# MainConnector.net
KiCad netlist of a schematic drawn in Altium Designer
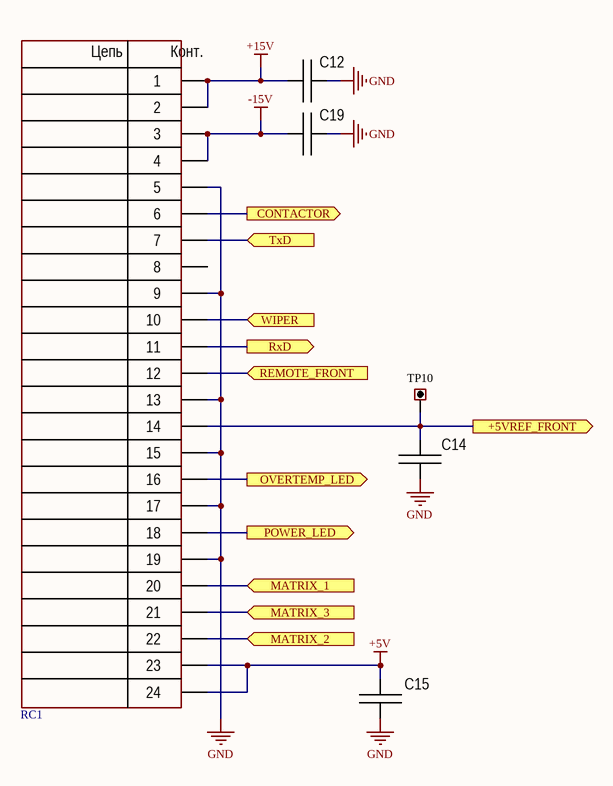
[diagram p0: MainConnector.SchDoc]

(export (version "E")
  (design (tool "Eeschema 10.0.6"))
  (components
    (comp (ref "C12")
      (value "~")
      (footprint "StandardCase:CAP: 1206")
      (fields
        (field (name "MANUFACTURER") "Yageo")
        (field (name "PARTNUMBER") "CC1206KRX7R9BB104")
        (field (name "VALUEMANUFACTURERPARTNUMBER") "Ceramic capacitor, 0.1μF, 1206")
      )
      (libsource (lib "Capacitor") (part "Ceramic_1206"))
    )
    (comp (ref "C14")
      (value "~")
      (footprint "StandardCase:CAP: 1206")
      (fields
        (field (name "MANUFACTURER") "Yageo")
        (field (name "PARTNUMBER") "CC1206KRX7R9BB104")
        (field (name "VALUEMANUFACTURERPARTNUMBER") "Ceramic capacitor, 0.1μF, 1206")
      )
      (libsource (lib "Capacitor") (part "Ceramic_1206"))
    )
    (comp (ref "C15")
      (value "~")
      (footprint "StandardCase:CAP: 1206")
      (fields
        (field (name "MANUFACTURER") "Yageo")
        (field (name "PARTNUMBER") "CC1206KRX7R9BB104")
        (field (name "VALUEMANUFACTURERPARTNUMBER") "Ceramic capacitor, 0.1μF, 1206")
      )
      (libsource (lib "Capacitor") (part "Ceramic_1206"))
    )
    (comp (ref "C19")
      (value "~")
      (footprint "StandardCase:CAP: 1206")
      (fields
        (field (name "MANUFACTURER") "Yageo")
        (field (name "PARTNUMBER") "CC1206KRX7R9BB104")
        (field (name "VALUEMANUFACTURERPARTNUMBER") "Ceramic capacitor, 0.1μF, 1206")
      )
      (libsource (lib "Capacitor") (part "Ceramic_1206"))
    )
    (comp (ref "RC1")
      (value "~")
      (footprint "DS1018-24 SIBX")
      (fields
        (field (name "VALUEMANUFACTURERPARTNUMBER") "Connector, DS1018-24 SIBX, 24 pin")
        (field (name "PARTNUMBER") "DS1018-24 SIBX")
      )
      (libsource (lib "FP_lib_SCH") (part "DS1018-24 SIBX"))
    )
    (comp (ref "TP10")
      (value "Test_Point")
      (footprint "FP_lib_PCB:Test_Point")
      (libsource (lib "FP_lib_SCH") (part "Test_Point"))
    )
  )
  (nets
    (net (code "1") (name "+5V") (class "Default")
      (node (ref "C15") (pin "2") (pinfunction "2_2") (pintype "power_in"))
      (node (ref "RC1") (pin "23") (pinfunction "23_23") (pintype "passive"))
      (node (ref "RC1") (pin "24") (pinfunction "24_24") (pintype "passive"))
    )
    (net (code "2") (name "+15V") (class "Default")
      (node (ref "C12") (pin "2") (pinfunction "2_2") (pintype "power_in"))
      (node (ref "RC1") (pin "1") (pinfunction "1_1") (pintype "passive"))
      (node (ref "RC1") (pin "2") (pinfunction "2_2") (pintype "passive"))
    )
    (net (code "3") (name "-15V") (class "Default")
      (node (ref "C19") (pin "1") (pinfunction "1_1") (pintype "power_in"))
      (node (ref "RC1") (pin "3") (pinfunction "3_3") (pintype "passive"))
      (node (ref "RC1") (pin "4") (pinfunction "4_4") (pintype "passive"))
    )
    (net (code "4") (name "/+5VREF_FRONT") (class "Default")
      (node (ref "C14") (pin "2") (pinfunction "2_2") (pintype "power_in"))
      (node (ref "RC1") (pin "14") (pinfunction "14_14") (pintype "passive"))
      (node (ref "TP10") (pin "1") (pinfunction "1_1") (pintype "passive"))
    )
    (net (code "5") (name "/CONTACTOR") (class "Default")
      (node (ref "RC1") (pin "6") (pinfunction "6_6") (pintype "passive"))
    )
    (net (code "6") (name "/MATRIX_1") (class "Default")
      (node (ref "RC1") (pin "20") (pinfunction "20_20") (pintype "passive"))
    )
    (net (code "7") (name "/MATRIX_2") (class "Default")
      (node (ref "RC1") (pin "22") (pinfunction "22_22") (pintype "passive"))
    )
    (net (code "8") (name "/MATRIX_3") (class "Default")
      (node (ref "RC1") (pin "21") (pinfunction "21_21") (pintype "passive"))
    )
    (net (code "9") (name "/OVERTEMP_LED") (class "Default")
      (node (ref "RC1") (pin "16") (pinfunction "16_16") (pintype "passive"))
    )
    (net (code "10") (name "/POWER_LED") (class "Default")
      (node (ref "RC1") (pin "18") (pinfunction "18_18") (pintype "passive"))
    )
    (net (code "11") (name "/REMOTE_FRONT") (class "Default")
      (node (ref "RC1") (pin "12") (pinfunction "12_12") (pintype "passive"))
    )
    (net (code "12") (name "/RxD") (class "Default")
      (node (ref "RC1") (pin "11") (pinfunction "11_11") (pintype "passive"))
    )
    (net (code "13") (name "/TxD") (class "Default")
      (node (ref "RC1") (pin "7") (pinfunction "7_7") (pintype "passive"))
    )
    (net (code "14") (name "/WIPER") (class "Default")
      (node (ref "RC1") (pin "10") (pinfunction "10_10") (pintype "passive"))
    )
    (net (code "15") (name "GND") (class "Default")
      (node (ref "C12") (pin "1") (pinfunction "1_1") (pintype "power_in"))
      (node (ref "C14") (pin "1") (pinfunction "1_1") (pintype "power_in"))
      (node (ref "C15") (pin "1") (pinfunction "1_1") (pintype "power_in"))
      (node (ref "C19") (pin "2") (pinfunction "2_2") (pintype "power_in"))
      (node (ref "RC1") (pin "13") (pinfunction "13_13") (pintype "passive"))
      (node (ref "RC1") (pin "15") (pinfunction "15_15") (pintype "passive"))
      (node (ref "RC1") (pin "17") (pinfunction "17_17") (pintype "passive"))
      (node (ref "RC1") (pin "19") (pinfunction "19_19") (pintype "passive"))
      (node (ref "RC1") (pin "5") (pinfunction "5_5") (pintype "passive"))
      (node (ref "RC1") (pin "9") (pinfunction "9_9") (pintype "passive"))
    )
    (net (code "16") (name "unconnected-(RC1-Pad8)") (class "Default")
      (node (ref "RC1") (pin "8") (pinfunction "8_8") (pintype "passive"))
    )
  )
)
